# Preisrahmen_Tibber.net
KiCad netlist of a schematic drawn in EAGLE
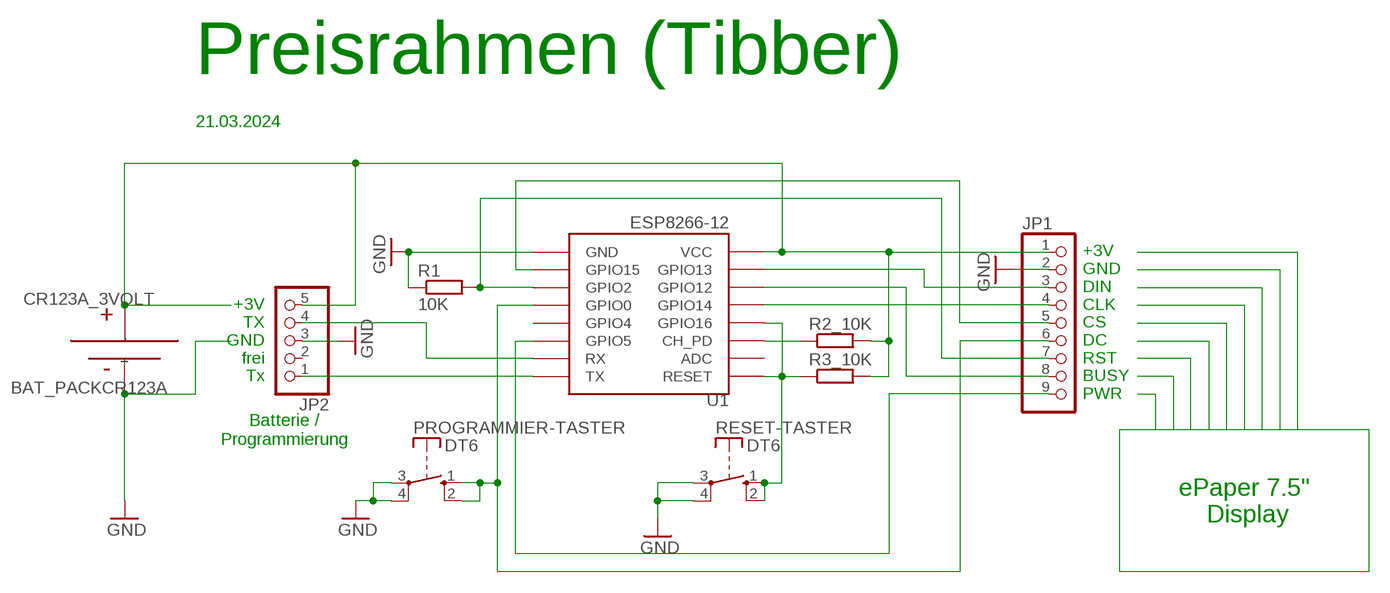
[diagram p0: schematic, sheet 1]

(export (version "E")
  (design (tool "Eeschema 10.0.6"))
  (components
    (comp (ref "CR123A_3VOLT")
      (value "BAT_PACKCR123A")
      (footprint "eagle-import:BH123A")
      (fields (field (name "MANUFACTURER") "MPD") (field (name "MPN") "BH123A"))
      (libsource (lib "eagle-import") (part "BAT_PACKCR123A"))
    )
    (comp (ref "JP1")
      (value "PINHD-1X9/90")
      (footprint "eagle-import:1X09_90")
      (libsource (lib "eagle-import") (part "PINHD-1X9/90"))
    )
    (comp (ref "JP2")
      (value "PINHD-1X5/90")
      (footprint "eagle-import:1X05_90")
      (libsource (lib "eagle-import") (part "PINHD-1X5/90"))
    )
    (comp (ref "PROGRAMMIER-TASTER")
      (value "DT6")
      (footprint "eagle-import:DT6")
      (libsource (lib "eagle-import") (part "DT6"))
    )
    (comp (ref "R1")
      (value "10K")
      (footprint "eagle-import:0207_7")
      (libsource (lib "eagle-import") (part "R-EU_0207/7"))
    )
    (comp (ref "R2_10K")
      (value "R-EU_0207/7")
      (footprint "eagle-import:0207_7")
      (libsource (lib "eagle-import") (part "R-EU_0207/7"))
    )
    (comp (ref "R3_10K")
      (value "R-EU_0207/7")
      (footprint "eagle-import:0207_7")
      (libsource (lib "eagle-import") (part "R-EU_0207/7"))
    )
    (comp (ref "RESET-TASTER")
      (value "DT6")
      (footprint "eagle-import:DT6")
      (libsource (lib "eagle-import") (part "DT6"))
    )
    (comp (ref "U1")
      (value "ESP8266-12")
      (footprint "eagle-import:ESP12")
      (libsource (lib "eagle-import") (part "ESP12"))
    )
  )
  (nets
    (net (code "1") (name "GND") (class "Default")
      (node (ref "CR123A_3VOLT") (pin "-") (pinfunction "-_-") (pintype "bidirectional"))
      (node (ref "JP1") (pin "2") (pinfunction "2_2") (pintype "passive"))
      (node (ref "JP2") (pin "3") (pinfunction "3_3") (pintype "passive"))
      (node (ref "PROGRAMMIER-TASTER") (pin "3") (pinfunction "P_3") (pintype "passive"))
      (node (ref "PROGRAMMIER-TASTER") (pin "4") (pinfunction "P_4") (pintype "passive"))
      (node (ref "R1") (pin "1") (pinfunction "1_1") (pintype "passive"))
      (node (ref "RESET-TASTER") (pin "3") (pinfunction "P_3") (pintype "passive"))
      (node (ref "RESET-TASTER") (pin "4") (pinfunction "P_4") (pintype "passive"))
      (node (ref "U1") (pin "GND") (pinfunction "GND_GND") (pintype "bidirectional"))
    )
    (net (code "2") (name "Net-(CR123A_3VOLT-Pad+)") (class "Default")
      (node (ref "CR123A_3VOLT") (pin "+") (pinfunction "+_+") (pintype "bidirectional"))
      (node (ref "JP1") (pin "1") (pinfunction "1_1") (pintype "passive"))
      (node (ref "JP2") (pin "5") (pinfunction "5_5") (pintype "passive"))
      (node (ref "R2_10K") (pin "2") (pinfunction "2_2") (pintype "passive"))
      (node (ref "R3_10K") (pin "2") (pinfunction "2_2") (pintype "passive"))
      (node (ref "U1") (pin "VCC") (pinfunction "VCC_VCC") (pintype "bidirectional"))
    )
    (net (code "3") (name "Net-(JP1-Pad3)") (class "Default")
      (node (ref "JP1") (pin "3") (pinfunction "3_3") (pintype "passive"))
      (node (ref "U1") (pin "GPIO13") (pinfunction "GPIO13_GPIO13") (pintype "bidirectional"))
    )
    (net (code "4") (name "Net-(JP1-Pad4)") (class "Default")
      (node (ref "JP1") (pin "4") (pinfunction "4_4") (pintype "passive"))
      (node (ref "U1") (pin "GPIO14") (pinfunction "GPIO14_GPIO14") (pintype "bidirectional"))
    )
    (net (code "5") (name "Net-(JP1-Pad5)") (class "Default")
      (node (ref "JP1") (pin "5") (pinfunction "5_5") (pintype "passive"))
      (node (ref "U1") (pin "GPIO15") (pinfunction "GPIO15_GPIO15") (pintype "bidirectional"))
    )
    (net (code "6") (name "Net-(JP1-Pad6)") (class "Default")
      (node (ref "JP1") (pin "6") (pinfunction "6_6") (pintype "passive"))
      (node (ref "PROGRAMMIER-TASTER") (pin "1") (pinfunction "S_1") (pintype "passive"))
      (node (ref "PROGRAMMIER-TASTER") (pin "2") (pinfunction "S_2") (pintype "passive"))
      (node (ref "U1") (pin "GPIO0") (pinfunction "GPIO0_GPIO0") (pintype "bidirectional"))
    )
    (net (code "7") (name "Net-(JP1-Pad7)") (class "Default")
      (node (ref "JP1") (pin "7") (pinfunction "7_7") (pintype "passive"))
      (node (ref "R1") (pin "2") (pinfunction "2_2") (pintype "passive"))
      (node (ref "U1") (pin "GPIO2") (pinfunction "GPIO2_GPIO2") (pintype "bidirectional"))
    )
    (net (code "8") (name "Net-(JP1-Pad8)") (class "Default")
      (node (ref "JP1") (pin "8") (pinfunction "8_8") (pintype "passive"))
      (node (ref "U1") (pin "GPIO12") (pinfunction "GPIO12_GPIO12") (pintype "bidirectional"))
    )
    (net (code "9") (name "Net-(JP1-Pad9)") (class "Default")
      (node (ref "JP1") (pin "9") (pinfunction "9_9") (pintype "passive"))
      (node (ref "U1") (pin "GPIO5") (pinfunction "GPIO5_GPIO5") (pintype "bidirectional"))
    )
    (net (code "10") (name "Net-(JP2-Pad1)") (class "Default")
      (node (ref "JP2") (pin "1") (pinfunction "1_1") (pintype "passive"))
      (node (ref "U1") (pin "TX") (pinfunction "TX_TX") (pintype "bidirectional"))
    )
    (net (code "11") (name "Net-(JP2-Pad4)") (class "Default")
      (node (ref "JP2") (pin "4") (pinfunction "4_4") (pintype "passive"))
      (node (ref "U1") (pin "RX") (pinfunction "RX_RX") (pintype "bidirectional"))
    )
    (net (code "12") (name "Net-(R2_10K-Pad1)") (class "Default")
      (node (ref "R2_10K") (pin "1") (pinfunction "1_1") (pintype "passive"))
      (node (ref "U1") (pin "CH_PD") (pinfunction "CH_PD_CH_PD") (pintype "bidirectional"))
    )
    (net (code "13") (name "Net-(R3_10K-Pad1)") (class "Default")
      (node (ref "R3_10K") (pin "1") (pinfunction "1_1") (pintype "passive"))
      (node (ref "RESET-TASTER") (pin "1") (pinfunction "S_1") (pintype "passive"))
      (node (ref "RESET-TASTER") (pin "2") (pinfunction "S_2") (pintype "passive"))
      (node (ref "U1") (pin "GPIO16") (pinfunction "GPIO16_GPIO16") (pintype "bidirectional"))
      (node (ref "U1") (pin "RESET") (pinfunction "RESET_RESET") (pintype "bidirectional"))
    )
    (net (code "14") (name "unconnected-(JP2-Pad2)") (class "Default")
      (node (ref "JP2") (pin "2") (pinfunction "2_2") (pintype "passive"))
    )
    (net (code "15") (name "unconnected-(U1-PadADC)") (class "Default")
      (node (ref "U1") (pin "ADC") (pinfunction "ADC_ADC") (pintype "bidirectional"))
    )
    (net (code "16") (name "unconnected-(U1-PadGPIO4)") (class "Default")
      (node (ref "U1") (pin "GPIO4") (pinfunction "GPIO4_GPIO4") (pintype "bidirectional"))
    )
  )
)
